# E-paper.net
KiCad netlist of a schematic drawn in Altium Designer
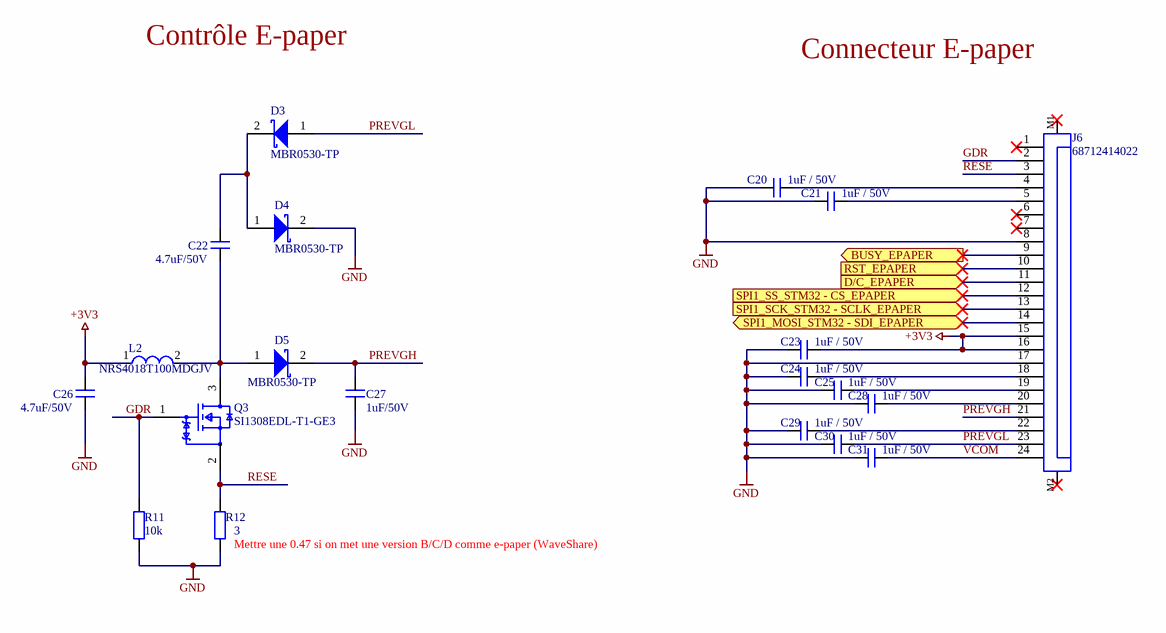
[diagram p0: E-paper.SchDoc]

(export (version "E")
  (design (tool "Eeschema 10.0.6"))
  (components
    (comp (ref "C20")
      (value "1uF / 50V")
      (footprint "WCAP-CSGP_0805_L2W1.25H0.8_Wave")
      (libsource (lib "Composants_Projet_2409") (part "CAPA"))
    )
    (comp (ref "C21")
      (value "1uF / 50V")
      (footprint "WCAP-CSGP_0805_L2W1.25H0.8_Wave")
      (libsource (lib "Composants_Projet_2409") (part "CAPA"))
    )
    (comp (ref "C22")
      (value "4.7uF/50V")
      (footprint "WCAP-CSGP_0805_L2W1.25H0.8_Wave")
      (libsource (lib "Composants_Projet_2409") (part "CAPA"))
    )
    (comp (ref "C23")
      (value "1uF / 50V")
      (footprint "WCAP-CSGP_0805_L2W1.25H0.8_Wave")
      (libsource (lib "Composants_Projet_2409") (part "CAPA"))
    )
    (comp (ref "C24")
      (value "1uF / 50V")
      (footprint "WCAP-CSGP_0805_L2W1.25H0.8_Wave")
      (libsource (lib "Composants_Projet_2409") (part "CAPA"))
    )
    (comp (ref "C25")
      (value "1uF / 50V")
      (footprint "WCAP-CSGP_0805_L2W1.25H0.8_Wave")
      (libsource (lib "Composants_Projet_2409") (part "CAPA"))
    )
    (comp (ref "C26")
      (value "4.7uF/50V")
      (footprint "WCAP-CSGP_0805_L2W1.25H0.8_Wave")
      (libsource (lib "Composants_Projet_2409") (part "CAPA"))
    )
    (comp (ref "C27")
      (value "1uF/50V")
      (footprint "WCAP-CSGP_0805_L2W1.25H0.8_Wave")
      (libsource (lib "Composants_Projet_2409") (part "CAPA"))
    )
    (comp (ref "C28")
      (value "1uF / 50V")
      (footprint "WCAP-CSGP_0805_L2W1.25H0.8_Wave")
      (libsource (lib "Composants_Projet_2409") (part "CAPA"))
    )
    (comp (ref "C29")
      (value "1uF / 50V")
      (footprint "WCAP-CSGP_0805_L2W1.25H0.8_Wave")
      (libsource (lib "Composants_Projet_2409") (part "CAPA"))
    )
    (comp (ref "C30")
      (value "1uF / 50V")
      (footprint "WCAP-CSGP_0805_L2W1.25H0.8_Wave")
      (libsource (lib "Composants_Projet_2409") (part "CAPA"))
    )
    (comp (ref "C31")
      (value "1uF / 50V")
      (footprint "WCAP-CSGP_0805_L2W1.25H0.8_Wave")
      (libsource (lib "Composants_Projet_2409") (part "CAPA"))
    )
    (comp (ref "D3")
      (value "MBR0530-TP")
      (footprint "ONSC-SOD-123-2-425-04_V")
      (libsource (lib "Composants_Projet_2409") (part "MBR0530-TP"))
    )
    (comp (ref "D4")
      (value "MBR0530-TP")
      (footprint "ONSC-SOD-123-2-425-04_V")
      (libsource (lib "Composants_Projet_2409") (part "MBR0530-TP"))
    )
    (comp (ref "D5")
      (value "MBR0530-TP")
      (footprint "ONSC-SOD-123-2-425-04_V")
      (libsource (lib "Composants_Projet_2409") (part "MBR0530-TP"))
    )
    (comp (ref "J6")
      (value "68712414022")
      (footprint "68712414022")
      (libsource (lib "Altium Content Vault") (part "FPC - 24P - 2MP"))
    )
    (comp (ref "L2")
      (value "NRS4018T100MDGJV")
      (footprint "FP-NR4018-MFG")
      (description "SMD Power Inductors for Automotive Applications 10uH ±20% 1.2A 0.18Ω")
      (fields (field (name "TOLERANCE") "20%"))
      (libsource (lib "Altium Content Vault") (part "725321dda6339637d4d059423bc1c3c"))
    )
    (comp (ref "Q3")
      (value "SI1308EDL-T1-GE3")
      (footprint "FP-5549-MFG")
      (description "MOSFET N-CH 30V 1.4A SC-70-3")
      (libsource (lib "Altium Content Vault") (part "e96677422f20f20903245877d22b385"))
    )
    (comp (ref "R11")
      (value "10k")
      (footprint "WRIS-PSMB_0805_L2W1.25H0.35")
      (description "Resistor")
      (fields (field (name "PUBLISHER") "Altium Limited"))
      (libsource (lib "Miscellaneous Devices") (part "Res2"))
    )
    (comp (ref "R12")
      (value "3")
      (footprint "WRIS-PSMB_0805_L2W1.25H0.35")
      (description "Resistor")
      (fields (field (name "PUBLISHER") "Altium Limited"))
      (libsource (lib "Miscellaneous Devices") (part "Res2"))
    )
  )
  (nets
    (net (code "1") (name "+3V3") (class "Default")
      (node (ref "C23") (pin "2") (pinfunction "-_2") (pintype "passive"))
      (node (ref "C26") (pin "1") (pinfunction "+_1") (pintype "passive"))
      (node (ref "J6") (pin "15") (pinfunction "15_15") (pintype "passive"))
      (node (ref "J6") (pin "16") (pinfunction "16_16") (pintype "passive"))
      (node (ref "L2") (pin "1") (pinfunction "1_1") (pintype "passive"))
    )
    (net (code "2") (name "/BUSY_EPAPER") (class "Default")
      (node (ref "J6") (pin "9") (pinfunction "9_9") (pintype "passive+no_connect"))
    )
    (net (code "3") (name "/D{slash}C_EPAPER") (class "Default")
      (node (ref "J6") (pin "11") (pinfunction "11_11") (pintype "passive+no_connect"))
    )
    (net (code "4") (name "/GDR") (class "Default")
      (node (ref "J6") (pin "2") (pinfunction "2_2") (pintype "passive"))
      (node (ref "Q3") (pin "1") (pinfunction "G_1") (pintype "passive"))
      (node (ref "R11") (pin "2") (pinfunction "2_2") (pintype "passive"))
    )
    (net (code "5") (name "/PREVGH") (class "Default")
      (node (ref "C27") (pin "1") (pinfunction "+_1") (pintype "passive"))
      (node (ref "D5") (pin "2") (pinfunction "C_2") (pintype "passive"))
      (node (ref "J6") (pin "21") (pinfunction "21_21") (pintype "passive"))
    )
    (net (code "6") (name "/PREVGL") (class "Default")
      (node (ref "C30") (pin "2") (pinfunction "-_2") (pintype "passive"))
      (node (ref "D3") (pin "1") (pinfunction "A_1") (pintype "passive"))
      (node (ref "J6") (pin "23") (pinfunction "23_23") (pintype "passive"))
    )
    (net (code "7") (name "/RESE") (class "Default")
      (node (ref "J6") (pin "3") (pinfunction "3_3") (pintype "passive"))
      (node (ref "Q3") (pin "2") (pinfunction "S_2") (pintype "passive"))
      (node (ref "R12") (pin "2") (pinfunction "2_2") (pintype "passive"))
    )
    (net (code "8") (name "/RST_EPAPER") (class "Default")
      (node (ref "J6") (pin "10") (pinfunction "10_10") (pintype "passive+no_connect"))
    )
    (net (code "9") (name "/SPI1_MOSI_STM32 - SDI_EPAPER") (class "Default")
      (node (ref "J6") (pin "14") (pinfunction "14_14") (pintype "passive+no_connect"))
    )
    (net (code "10") (name "/SPI1_SCK_STM32 - SCLK_EPAPER") (class "Default")
      (node (ref "J6") (pin "13") (pinfunction "13_13") (pintype "passive+no_connect"))
    )
    (net (code "11") (name "/SPI1_SS_STM32 - CS_EPAPER") (class "Default")
      (node (ref "J6") (pin "12") (pinfunction "12_12") (pintype "passive+no_connect"))
    )
    (net (code "12") (name "/VCOM") (class "Default")
      (node (ref "C31") (pin "2") (pinfunction "-_2") (pintype "passive"))
      (node (ref "J6") (pin "24") (pinfunction "24_24") (pintype "passive"))
    )
    (net (code "13") (name "GND") (class "Default")
      (node (ref "C20") (pin "1") (pinfunction "+_1") (pintype "passive"))
      (node (ref "C21") (pin "1") (pinfunction "+_1") (pintype "passive"))
      (node (ref "C23") (pin "1") (pinfunction "+_1") (pintype "passive"))
      (node (ref "C24") (pin "1") (pinfunction "+_1") (pintype "passive"))
      (node (ref "C25") (pin "1") (pinfunction "+_1") (pintype "passive"))
      (node (ref "C26") (pin "2") (pinfunction "-_2") (pintype "passive"))
      (node (ref "C27") (pin "2") (pinfunction "-_2") (pintype "passive"))
      (node (ref "C28") (pin "1") (pinfunction "+_1") (pintype "passive"))
      (node (ref "C29") (pin "1") (pinfunction "+_1") (pintype "passive"))
      (node (ref "C30") (pin "1") (pinfunction "+_1") (pintype "passive"))
      (node (ref "C31") (pin "1") (pinfunction "+_1") (pintype "passive"))
      (node (ref "D4") (pin "2") (pinfunction "C_2") (pintype "passive"))
      (node (ref "J6") (pin "17") (pinfunction "17_17") (pintype "passive"))
      (node (ref "J6") (pin "8") (pinfunction "8_8") (pintype "passive"))
      (node (ref "R11") (pin "1") (pinfunction "1_1") (pintype "passive"))
      (node (ref "R12") (pin "1") (pinfunction "1_1") (pintype "passive"))
    )
    (net (code "14") (name "Net-(C20--)") (class "Default")
      (node (ref "C20") (pin "2") (pinfunction "-_2") (pintype "passive"))
      (node (ref "J6") (pin "4") (pinfunction "4_4") (pintype "passive"))
    )
    (net (code "15") (name "Net-(C21--)") (class "Default")
      (node (ref "C21") (pin "2") (pinfunction "-_2") (pintype "passive"))
      (node (ref "J6") (pin "5") (pinfunction "5_5") (pintype "passive"))
    )
    (net (code "16") (name "Net-(C22-+)") (class "Default")
      (node (ref "C22") (pin "1") (pinfunction "+_1") (pintype "passive"))
      (node (ref "D3") (pin "2") (pinfunction "C_2") (pintype "passive"))
      (node (ref "D4") (pin "1") (pinfunction "A_1") (pintype "passive"))
    )
    (net (code "17") (name "Net-(C22--)") (class "Default")
      (node (ref "C22") (pin "2") (pinfunction "-_2") (pintype "passive"))
      (node (ref "D5") (pin "1") (pinfunction "A_1") (pintype "passive"))
      (node (ref "L2") (pin "2") (pinfunction "2_2") (pintype "passive"))
      (node (ref "Q3") (pin "3") (pinfunction "D_3") (pintype "passive"))
    )
    (net (code "18") (name "Net-(C24--)") (class "Default")
      (node (ref "C24") (pin "2") (pinfunction "-_2") (pintype "passive"))
      (node (ref "J6") (pin "18") (pinfunction "18_18") (pintype "passive"))
    )
    (net (code "19") (name "Net-(C25--)") (class "Default")
      (node (ref "C25") (pin "2") (pinfunction "-_2") (pintype "passive"))
      (node (ref "J6") (pin "19") (pinfunction "19_19") (pintype "passive"))
    )
    (net (code "20") (name "Net-(C28--)") (class "Default")
      (node (ref "C28") (pin "2") (pinfunction "-_2") (pintype "passive"))
      (node (ref "J6") (pin "20") (pinfunction "20_20") (pintype "passive"))
    )
    (net (code "21") (name "Net-(C29--)") (class "Default")
      (node (ref "C29") (pin "2") (pinfunction "-_2") (pintype "passive"))
      (node (ref "J6") (pin "22") (pinfunction "22_22") (pintype "passive"))
    )
    (net (code "22") (name "unconnected-(J6-Pad1)") (class "Default")
      (node (ref "J6") (pin "1") (pinfunction "1_1") (pintype "passive+no_connect"))
    )
    (net (code "23") (name "unconnected-(J6-Pad6)") (class "Default")
      (node (ref "J6") (pin "6") (pinfunction "6_6") (pintype "passive+no_connect"))
    )
    (net (code "24") (name "unconnected-(J6-Pad7)") (class "Default")
      (node (ref "J6") (pin "7") (pinfunction "7_7") (pintype "passive+no_connect"))
    )
    (net (code "25") (name "unconnected-(J6-PadM1)") (class "Default")
      (node (ref "J6") (pin "M1") (pinfunction "M1_M1") (pintype "passive+no_connect"))
    )
    (net (code "26") (name "unconnected-(J6-PadM2)") (class "Default")
      (node (ref "J6") (pin "M2") (pinfunction "M2_M2") (pintype "passive+no_connect"))
    )
  )
)
